# Separator-B.net
KiCad netlist of a schematic drawn in EAGLE
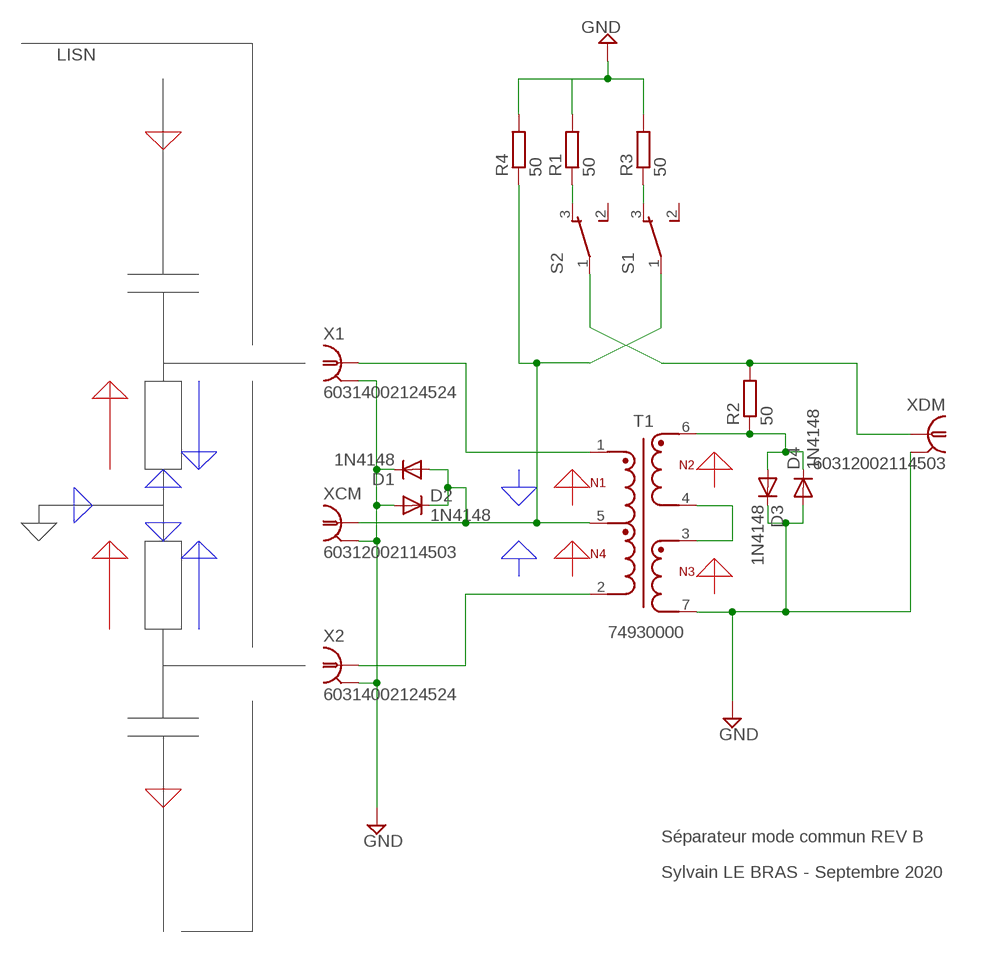
[diagram p0: schematic, sheet 1]

(export (version "E")
  (design (tool "Eeschema 10.0.6"))
  (components
    (comp (ref "D1")
      (value "1N4148")
      (footprint "eagle-import:SOD123")
      (libsource (lib "eagle-import") (part "DIODE-SOD123"))
    )
    (comp (ref "D2")
      (value "1N4148")
      (footprint "eagle-import:SOD123")
      (libsource (lib "eagle-import") (part "DIODE-SOD123"))
    )
    (comp (ref "D3")
      (value "1N4148")
      (footprint "eagle-import:SOD123")
      (libsource (lib "eagle-import") (part "DIODE-SOD123"))
    )
    (comp (ref "D4")
      (value "1N4148")
      (footprint "eagle-import:SOD123")
      (libsource (lib "eagle-import") (part "DIODE-SOD123"))
    )
    (comp (ref "R1")
      (value "50")
      (footprint "eagle-import:R0805")
      (libsource (lib "eagle-import") (part "R-EU_R0805"))
    )
    (comp (ref "R2")
      (value "50")
      (footprint "eagle-import:R0805")
      (libsource (lib "eagle-import") (part "R-EU_R0805"))
    )
    (comp (ref "R3")
      (value "50")
      (footprint "eagle-import:R0805")
      (libsource (lib "eagle-import") (part "R-EU_R0805"))
    )
    (comp (ref "R4")
      (value "50")
      (footprint "eagle-import:R0805")
      (libsource (lib "eagle-import") (part "R-EU_R0805"))
    )
    (comp (ref "S1")
      (value "450301014042")
      (footprint "eagle-import:450301014042")
      (libsource (lib "eagle-import") (part "450301014042"))
    )
    (comp (ref "S2")
      (value "450301014042")
      (footprint "eagle-import:450301014042")
      (libsource (lib "eagle-import") (part "450301014042"))
    )
    (comp (ref "T1")
      (value "74930000")
      (footprint "eagle-import:WE-STST_74930000")
      (libsource (lib "eagle-import") (part "WE-STST_4532_74930000"))
    )
    (comp (ref "X1")
      (value "60314002124524")
      (footprint "eagle-import:LTI-SASF54GT")
      (libsource (lib "eagle-import") (part "LTI-SASF54GT"))
    )
    (comp (ref "X2")
      (value "60314002124524")
      (footprint "eagle-import:LTI-SASF54GT")
      (libsource (lib "eagle-import") (part "LTI-SASF54GT"))
    )
    (comp (ref "XCM")
      (value "60312002114503")
      (footprint "eagle-import:LTI-SASF54GT")
      (libsource (lib "eagle-import") (part "LTI-SASF54GT"))
    )
    (comp (ref "XDM")
      (value "60312002114503")
      (footprint "eagle-import:LTI-SASF54GT")
      (libsource (lib "eagle-import") (part "LTI-SASF54GT"))
    )
  )
  (nets
    (net (code "1") (name "GND") (class "Default")
      (node (ref "D1") (pin "C") (pinfunction "C_C") (pintype "passive"))
      (node (ref "D2") (pin "A") (pinfunction "A_A") (pintype "passive"))
      (node (ref "D3") (pin "C") (pinfunction "C_C") (pintype "passive"))
      (node (ref "D4") (pin "A") (pinfunction "A_A") (pintype "passive"))
      (node (ref "R1") (pin "2") (pinfunction "2_2") (pintype "passive"))
      (node (ref "R3") (pin "2") (pinfunction "2_2") (pintype "passive"))
      (node (ref "R4") (pin "2") (pinfunction "2_2") (pintype "passive"))
      (node (ref "T1") (pin "7") (pinfunction "7_7") (pintype "passive"))
      (node (ref "X1") (pin "2") (pinfunction "GND_2") (pintype "power_in"))
      (node (ref "X2") (pin "2") (pinfunction "GND_2") (pintype "power_in"))
      (node (ref "XCM") (pin "2") (pinfunction "GND_2") (pintype "power_in"))
      (node (ref "XDM") (pin "2") (pinfunction "GND_2") (pintype "power_in"))
    )
    (net (code "2") (name "Net-(D1-PadA)") (class "Default")
      (node (ref "D1") (pin "A") (pinfunction "A_A") (pintype "passive"))
      (node (ref "D2") (pin "C") (pinfunction "C_C") (pintype "passive"))
      (node (ref "R4") (pin "1") (pinfunction "1_1") (pintype "passive"))
      (node (ref "S1") (pin "1") (pinfunction "1_1") (pintype "passive"))
      (node (ref "T1") (pin "5") (pinfunction "5_5") (pintype "passive"))
      (node (ref "XCM") (pin "1") (pinfunction "1_1") (pintype "passive"))
    )
    (net (code "3") (name "Net-(D3-PadA)") (class "Default")
      (node (ref "D3") (pin "A") (pinfunction "A_A") (pintype "passive"))
      (node (ref "D4") (pin "C") (pinfunction "C_C") (pintype "passive"))
      (node (ref "R2") (pin "1") (pinfunction "1_1") (pintype "passive"))
      (node (ref "T1") (pin "6") (pinfunction "6_6") (pintype "passive"))
    )
    (net (code "4") (name "Net-(R1-Pad1)") (class "Default")
      (node (ref "R1") (pin "1") (pinfunction "1_1") (pintype "passive"))
      (node (ref "S2") (pin "3") (pinfunction "3_3") (pintype "passive"))
    )
    (net (code "5") (name "Net-(R2-Pad2)") (class "Default")
      (node (ref "R2") (pin "2") (pinfunction "2_2") (pintype "passive"))
      (node (ref "S2") (pin "1") (pinfunction "1_1") (pintype "passive"))
      (node (ref "XDM") (pin "1") (pinfunction "1_1") (pintype "passive"))
    )
    (net (code "6") (name "Net-(R3-Pad1)") (class "Default")
      (node (ref "R3") (pin "1") (pinfunction "1_1") (pintype "passive"))
      (node (ref "S1") (pin "3") (pinfunction "3_3") (pintype "passive"))
    )
    (net (code "7") (name "Net-(T1-Pad1)") (class "Default")
      (node (ref "T1") (pin "1") (pinfunction "1_1") (pintype "passive"))
      (node (ref "X1") (pin "1") (pinfunction "1_1") (pintype "passive"))
    )
    (net (code "8") (name "Net-(T1-Pad2)") (class "Default")
      (node (ref "T1") (pin "2") (pinfunction "2_2") (pintype "passive"))
      (node (ref "X2") (pin "1") (pinfunction "1_1") (pintype "passive"))
    )
    (net (code "9") (name "Net-(T1-Pad3)") (class "Default")
      (node (ref "T1") (pin "3") (pinfunction "3_3") (pintype "passive"))
      (node (ref "T1") (pin "4") (pinfunction "4_4") (pintype "passive"))
    )
    (net (code "10") (name "unconnected-(S1-Pad2)") (class "Default")
      (node (ref "S1") (pin "2") (pinfunction "2_2") (pintype "passive"))
    )
    (net (code "11") (name "unconnected-(S2-Pad2)") (class "Default")
      (node (ref "S2") (pin "2") (pinfunction "2_2") (pintype "passive"))
    )
  )
)
